# EPS_3V3_EMI-Filter_Out.net
KiCad netlist of a schematic drawn in Altium Designer
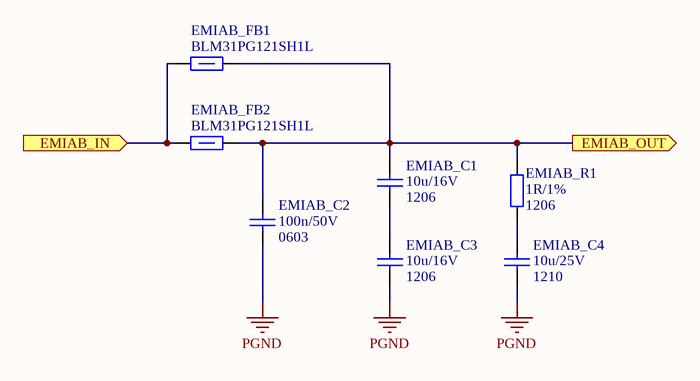
[diagram p0: EPS_3V3_EMI-Filter_Out.SchDoc]

(export (version "E")
  (design (tool "Eeschema 10.0.6"))
  (components
    (comp (ref "EMIAB_C1")
      (value "10u/16V")
      (footprint "SMD_Capacitor_1206")
      (description "Ceramic Cap Kemet COTS 10u/16V X7R 1206")
      (fields
        (field (name "MANUFACTURERPARTNUMBER") "C1206T106K4RACTU")
        (field (name "MANUFACTURER") "Kemet")
        (field (name "PACKGE") "1206")
      )
      (libsource (lib "capacitors") (part "Cer_C1206T106K4RACTU"))
    )
    (comp (ref "EMIAB_C2")
      (value "100n/50V")
      (footprint "SMD_Capacitor_0603")
      (description "Ceramic Cap Kemet COTS 100n/50V X7R 0603")
      (fields
        (field (name "MANUFACTURER") "Kemet")
        (field (name "MANUFACTURERPARTNUMBER") "C0603T104K5RALTU")
        (field (name "PACKAGE") "0603")
      )
      (libsource (lib "capacitors") (part "Cer_C0603T104K5RALTU"))
    )
    (comp (ref "EMIAB_C3")
      (value "10u/16V")
      (footprint "SMD_Capacitor_1206")
      (description "Ceramic Cap Kemet COTS 10u/16V X7R 1206")
      (fields
        (field (name "MANUFACTURERPARTNUMBER") "C1206T106K4RACTU")
        (field (name "MANUFACTURER") "Kemet")
        (field (name "PACKGE") "1206")
      )
      (libsource (lib "capacitors") (part "Cer_C1206T106K4RACTU"))
    )
    (comp (ref "EMIAB_C4")
      (value "10u/25V")
      (footprint "SMD_Capacitor_1210")
      (description "Ceramic Cap Murata Automotive 10u/25V X7R 1210")
      (fields
        (field (name "MANUFACTURER") "Murata")
        (field (name "MANUFACTURERPARTNUMBER") "GCJ32ER71E106KA12L")
        (field (name "PACKAGE") "1210")
      )
      (libsource (lib "capacitors") (part "Cer_GCJ32ER71E106KA12L"))
    )
    (comp (ref "EMIAB_FB1")
      (value "120R/100MHz")
      (footprint "SMD_FerriteBead_1206")
      (description "Ferrite bead, 1206, 0.02HM, 3.5A.")
      (fields (field (name "MANUFACTURER") "Murata") (field (name "MANUFACTURERPARTNUMBER") "BLM31PG121SH1L"))
      (libsource (lib "inductors") (part "BLM31PG121SH1L"))
    )
    (comp (ref "EMIAB_FB2")
      (value "120R/100MHz")
      (footprint "SMD_FerriteBead_1206")
      (description "Ferrite bead, 1206, 0.02HM, 3.5A.")
      (fields (field (name "MANUFACTURER") "Murata") (field (name "MANUFACTURERPARTNUMBER") "BLM31PG121SH1L"))
      (libsource (lib "inductors") (part "BLM31PG121SH1L"))
    )
    (comp (ref "EMIAB_R1")
      (value "1R/1%")
      (footprint "SMD_Resistor_1206")
      (description "1R/1% Vishay CRCW 1206 Resistor. 250mW, 100ppm, 200V.")
      (fields
        (field (name "MANUFACTURERPARTNUMBER") "CRCW12061R00FKxxxx")
        (field (name "MANUFACTURER") "Vishay")
        (field (name "PACKAGE") "1206")
      )
      (libsource (lib "resistors") (part "CRCW12061R00FKxxxx"))
    )
  )
  (nets
    (net (code "1") (name "/EMIAB_IN") (class "Default")
      (node (ref "EMIAB_FB1") (pin "2") (pinfunction "2_2") (pintype "passive"))
      (node (ref "EMIAB_FB2") (pin "2") (pinfunction "2_2") (pintype "passive"))
    )
    (net (code "2") (name "/EMIAB_OUT") (class "Default")
      (node (ref "EMIAB_C1") (pin "1") (pinfunction "1_1") (pintype "passive"))
      (node (ref "EMIAB_C2") (pin "1") (pinfunction "1_1") (pintype "passive"))
      (node (ref "EMIAB_FB1") (pin "1") (pinfunction "1_1") (pintype "passive"))
      (node (ref "EMIAB_FB2") (pin "1") (pinfunction "1_1") (pintype "passive"))
      (node (ref "EMIAB_R1") (pin "1") (pinfunction "1_1") (pintype "passive"))
    )
    (net (code "3") (name "Net-(EMIAB_C1-Pad2)") (class "Default")
      (node (ref "EMIAB_C1") (pin "2") (pinfunction "2_2") (pintype "passive"))
      (node (ref "EMIAB_C3") (pin "1") (pinfunction "1_1") (pintype "passive"))
    )
    (net (code "4") (name "Net-(EMIAB_C4-Pad1)") (class "Default")
      (node (ref "EMIAB_C4") (pin "1") (pinfunction "1_1") (pintype "passive"))
      (node (ref "EMIAB_R1") (pin "2") (pinfunction "2_2") (pintype "passive"))
    )
    (net (code "5") (name "PGND") (class "Default")
      (node (ref "EMIAB_C2") (pin "2") (pinfunction "2_2") (pintype "passive"))
      (node (ref "EMIAB_C3") (pin "2") (pinfunction "2_2") (pintype "passive"))
      (node (ref "EMIAB_C4") (pin "2") (pinfunction "2_2") (pintype "passive"))
    )
  )
)
